# Scintillator_Circuit.net
KiCad netlist of a schematic drawn in Altium Designer
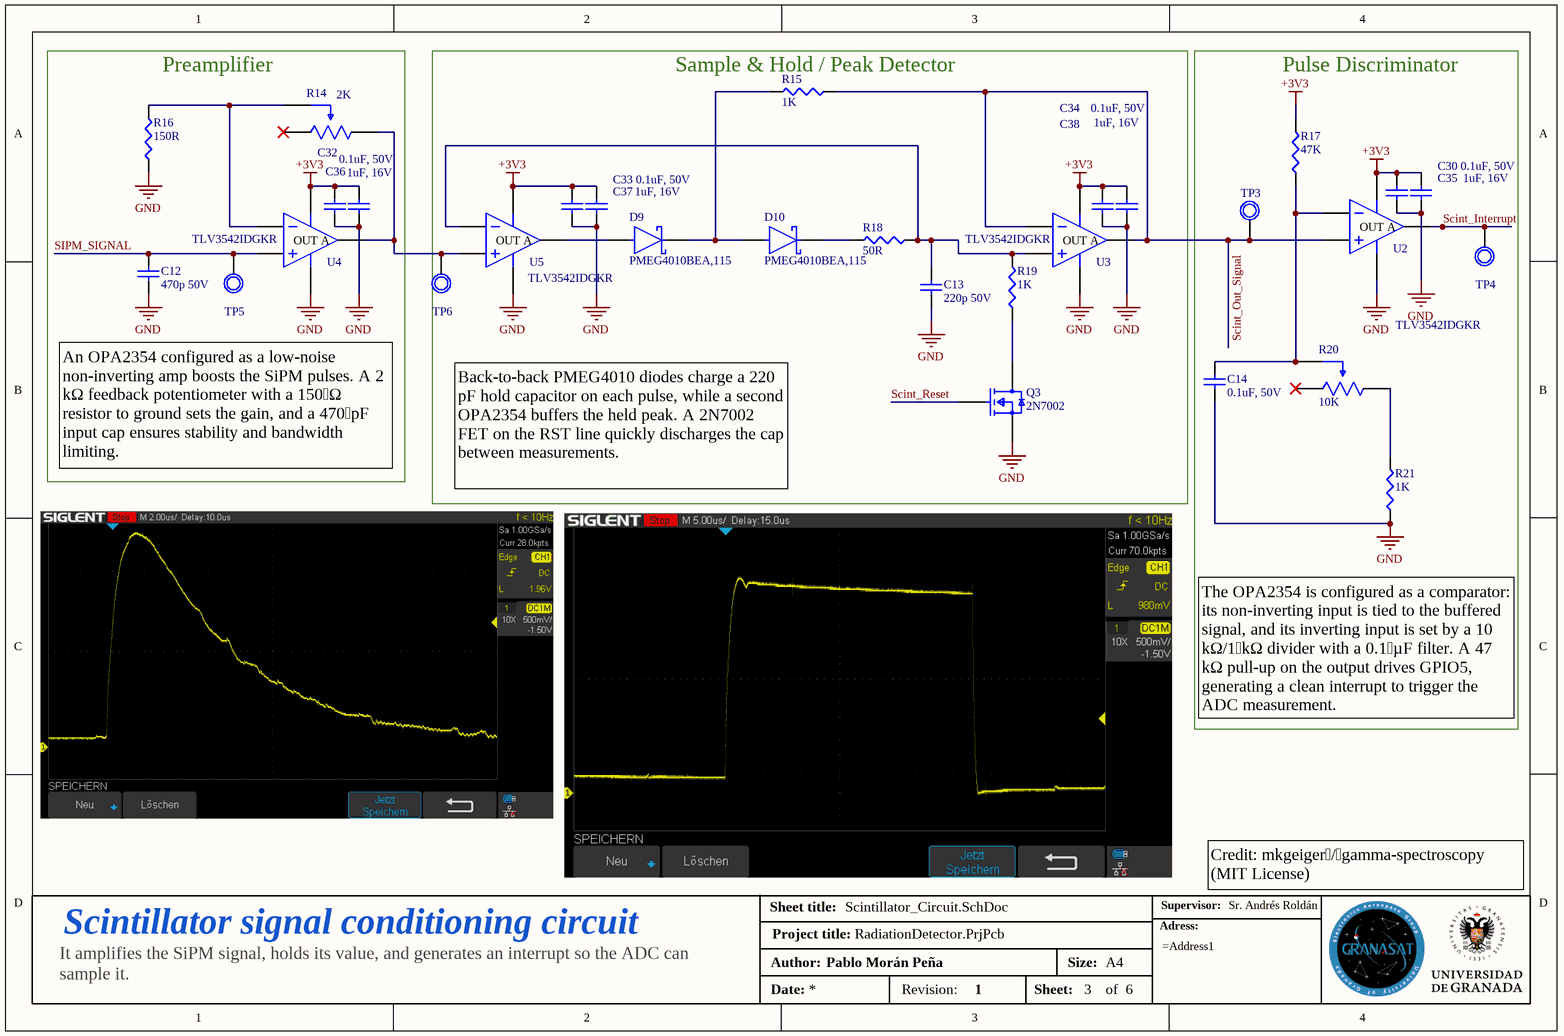
[diagram p0: Scintillator_Circuit.SchDoc]

(export (version "E")
  (design (tool "Eeschema 10.0.6"))
  (components
    (comp (ref "C12")
      (value "470p 50V")
      (footprint "CAP 0402_1005")
      (description "CAP CER 470PF 50V X7R 0402")
      (fields
        (field (name "MANUFACTURER") "Samsung")
        (field (name "MANUFACTURER PART NUMBER") "CL05B471KB5VPNC")
      )
      (libsource (lib "Schlib") (part "CL05B471KB5VPNC"))
    )
    (comp (ref "C13")
      (value "220p 50V")
      (footprint "CAP 0402_1005")
      (description "CAP CER 220PF 50V X7R 0402")
      (fields
        (field (name "MANUFACTURER") "Samsung")
        (field (name "MANUFACTURER PART NUMBER") "CL05B221KB5NNNC")
      )
      (libsource (lib "Schlib") (part "CL05B221KB5NNNC"))
    )
    (comp (ref "C14")
      (value "0.1uF, 50V")
      (footprint "CAP 0402_1005")
      (description "CAP CER 0.1UF 50V X7R 0402")
      (fields
        (field (name "MANUFACTURER") "Samsung")
        (field (name "MANUFACTURER PART NUMBER") "CL05B104KB5NNNC")
      )
      (libsource (lib "Schlib") (part "CL05B104KB5NNNC"))
    )
    (comp (ref "C30")
      (value "0.1uF, 50V")
      (footprint "CAP 0402_1005")
      (description "CAP CER 0.1UF 50V X7R 0402")
      (fields
        (field (name "MANUFACTURER") "Samsung")
        (field (name "MANUFACTURER PART NUMBER") "CL05B104KB5NNNC")
      )
      (libsource (lib "Schlib") (part "CL05B104KB5NNNC"))
    )
    (comp (ref "C32")
      (value "0.1uF, 50V")
      (footprint "CAP 0402_1005")
      (description "CAP CER 0.1UF 50V X7R 0402")
      (fields
        (field (name "MANUFACTURER") "Samsung")
        (field (name "MANUFACTURER PART NUMBER") "CL05B104KB5NNNC")
      )
      (libsource (lib "Schlib") (part "CL05B104KB5NNNC"))
    )
    (comp (ref "C33")
      (value "0.1uF, 50V")
      (footprint "CAP 0402_1005")
      (description "CAP CER 0.1UF 50V X7R 0402")
      (fields
        (field (name "MANUFACTURER") "Samsung")
        (field (name "MANUFACTURER PART NUMBER") "CL05B104KB5NNNC")
      )
      (libsource (lib "Schlib") (part "CL05B104KB5NNNC"))
    )
    (comp (ref "C34")
      (value "0.1uF, 50V")
      (footprint "CAP 0402_1005")
      (description "CAP CER 0.1UF 50V X7R 0402")
      (fields
        (field (name "MANUFACTURER") "Samsung")
        (field (name "MANUFACTURER PART NUMBER") "CL05B104KB5NNNC")
      )
      (libsource (lib "Schlib") (part "CL05B104KB5NNNC"))
    )
    (comp (ref "C35")
      (value "1uF, 16V")
      (footprint "CAP 0402_1005")
      (description "CAP CER 1UF 16V X5R 0402")
      (fields
        (field (name "MANUFACTURER") "Samsung Electro-Mechanics")
        (field (name "MANUFACTURER PART NUMBER") "CL05A105KO5NNNC")
      )
      (libsource (lib "Schlib") (part "CL05A105KO5NNNC"))
    )
    (comp (ref "C36")
      (value "1uF, 16V")
      (footprint "CAP 0402_1005")
      (description "CAP CER 1UF 16V X5R 0402")
      (fields
        (field (name "MANUFACTURER") "Samsung Electro-Mechanics")
        (field (name "MANUFACTURER PART NUMBER") "CL05A105KO5NNNC")
      )
      (libsource (lib "Schlib") (part "CL05A105KO5NNNC"))
    )
    (comp (ref "C37")
      (value "1uF, 16V")
      (footprint "CAP 0402_1005")
      (description "CAP CER 1UF 16V X5R 0402")
      (fields
        (field (name "MANUFACTURER") "Samsung Electro-Mechanics")
        (field (name "MANUFACTURER PART NUMBER") "CL05A105KO5NNNC")
      )
      (libsource (lib "Schlib") (part "CL05A105KO5NNNC"))
    )
    (comp (ref "C38")
      (value "1uF, 16V")
      (footprint "CAP 0402_1005")
      (description "CAP CER 1UF 16V X5R 0402")
      (fields
        (field (name "MANUFACTURER") "Samsung Electro-Mechanics")
        (field (name "MANUFACTURER PART NUMBER") "CL05A105KO5NNNC")
      )
      (libsource (lib "Schlib") (part "CL05A105KO5NNNC"))
    )
    (comp (ref "D9")
      (value "PMEG4010BEA,115")
      (footprint "SOD2512X110N")
      (description "DIODE SCHOTTKY 40V 1A SOD323")
      (fields (field (name "MANUFACTURER") "Nexperia") (field (name "LCSC PART NUMBER") "C36975"))
      (libsource (lib "Schlib") (part "PMEG4010BEA,115"))
    )
    (comp (ref "D10")
      (value "PMEG4010BEA,115")
      (footprint "SOD2512X110N")
      (description "DIODE SCHOTTKY 40V 1A SOD323")
      (fields (field (name "MANUFACTURER") "Nexperia") (field (name "LCSC PART NUMBER") "C36975"))
      (libsource (lib "Schlib") (part "PMEG4010BEA,115"))
    )
    (comp (ref "Q3")
      (value "2N7002")
      (footprint "SOT95P240X111-3N")
      (description "MOSFET SOT23 N 60V 5OHM 150C")
      (fields
        (field (name "MANUFACTURER") "ON Semiconductor / Fairchild")
        (field (name "LCSC PART NUMBER") "C124475")
      )
      (libsource (lib "Schlib") (part "2N7002"))
    )
    (comp (ref "R14")
      (value "2K")
      (footprint "TRIM_3314J-1-202E")
      (description "TRIMMER 2K OHM 0.25W J LEAD TOP")
      (fields (field (name "MANUFACTURER") "Bourns") (field (name "MANUFACTURER PART NUMBER") "3314J-1-202E"))
      (libsource (lib "Schlib") (part "3314J-1-202E"))
    )
    (comp (ref "R15")
      (value "1K")
      (footprint "RESC1005X37N")
      (description "RES SMD 1K OHM 5% 1/16W 0402")
      (fields
        (field (name "MANUFACTURER") "Yageo")
        (field (name "MANUFACTURER PART NUMBER") "AC0402JR-071KL")
      )
      (libsource (lib "Schlib") (part "AC0402JR-071KL"))
    )
    (comp (ref "R16")
      (value "150R")
      (footprint "RESC1005X37N")
      (description "RES SMD 150 OHM 1% 1/16W 0402")
      (fields
        (field (name "MANUFACTURER") "Yageo")
        (field (name "MANUFACTURER PART NUMBER") "AC0402FR-07150RL")
      )
      (libsource (lib "Schlib") (part "AC0402FR-07150RL"))
    )
    (comp (ref "R17")
      (value "47K")
      (footprint "RESC1005X37N")
      (description "RES SMD 47K OHM 1% 1/16W 0402")
      (fields
        (field (name "MANUFACTURER") "Yageo")
        (field (name "MANUFACTURER PART NUMBER") "AC0402FR-0747KL")
      )
      (libsource (lib "Schlib") (part "AC0402FR-0747KL"))
    )
    (comp (ref "R18")
      (value "50R")
      (footprint "RESC1005X37N")
      (description "RES SMD 50 OHM 0.1% 1/16W 0402")
      (fields
        (field (name "MANUFACTURER") "Yageo")
        (field (name "MANUFACTURER PART NUMBER") "RT0402BRE0750RL")
      )
      (libsource (lib "Schlib") (part "RT0402BRE0750RL"))
    )
    (comp (ref "R19")
      (value "1K")
      (footprint "RESC1005X37N")
      (description "RES SMD 1K OHM 5% 1/16W 0402")
      (fields
        (field (name "MANUFACTURER") "Yageo")
        (field (name "MANUFACTURER PART NUMBER") "AC0402JR-071KL")
      )
      (libsource (lib "Schlib") (part "AC0402JR-071KL"))
    )
    (comp (ref "R20")
      (value "10K")
      (footprint "TS53YL_VIS")
      (description "TRIMMER 10K OHM 0.25W GW TOP ADJ")
      (fields
        (field (name "MANUFACTURER") "Vishay")
        (field (name "MANUFACTURER PART NUMBER") "TS53YL103MR10")
      )
      (libsource (lib "Schlib") (part "TS53YL103MR10"))
    )
    (comp (ref "R21")
      (value "1K")
      (footprint "RESC1005X37N")
      (description "RES SMD 1K OHM 5% 1/16W 0402")
      (fields
        (field (name "MANUFACTURER") "Yageo")
        (field (name "MANUFACTURER PART NUMBER") "AC0402JR-071KL")
      )
      (libsource (lib "Schlib") (part "AC0402JR-071KL"))
    )
    (comp (ref "TP3")
      (value "Testpoint")
      (footprint "Testpoint")
      (libsource (lib "Schlib") (part "Testpoint"))
    )
    (comp (ref "TP4")
      (value "Testpoint")
      (footprint "Testpoint")
      (libsource (lib "Schlib") (part "Testpoint"))
    )
    (comp (ref "TP5")
      (value "Testpoint")
      (footprint "Testpoint")
      (libsource (lib "Schlib") (part "Testpoint"))
    )
    (comp (ref "TP6")
      (value "Testpoint")
      (footprint "Testpoint")
      (libsource (lib "Schlib") (part "Testpoint"))
    )
    (comp (ref "U2")
      (value "TLV3542IDGKR")
      (footprint "DGK0008A_M")
      (description "200MHz Rail-to-Rail I/O, CMOS Operational Amplifier for Cost-Sensitive Systems")
      (fields
        (field (name "MANUFACTURER") "Texas Instruments")
        (field (name "MANUFACTURER PART NUMBER") "OPA2354AIDGKR")
      )
      (libsource (lib "Schlib") (part "TLV3542IDGKR"))
    )
    (comp (ref "U3")
      (value "TLV3542IDGKR")
      (footprint "DGK0008A_M")
      (description "200MHz Rail-to-Rail I/O, CMOS Operational Amplifier for Cost-Sensitive Systems")
      (fields
        (field (name "MANUFACTURER") "Texas Instruments")
        (field (name "MANUFACTURER PART NUMBER") "OPA2354AIDGKR")
      )
      (libsource (lib "Schlib") (part "TLV3542IDGKR"))
    )
    (comp (ref "U4")
      (value "TLV3542IDGKR")
      (footprint "DGK0008A_M")
      (description "200MHz Rail-to-Rail I/O, CMOS Operational Amplifier for Cost-Sensitive Systems")
      (fields
        (field (name "MANUFACTURER") "Texas Instruments")
        (field (name "MANUFACTURER PART NUMBER") "OPA2354AIDGKR")
      )
      (libsource (lib "Schlib") (part "TLV3542IDGKR"))
    )
    (comp (ref "U5")
      (value "TLV3542IDGKR")
      (footprint "DGK0008A_M")
      (description "200MHz Rail-to-Rail I/O, CMOS Operational Amplifier for Cost-Sensitive Systems")
      (fields
        (field (name "MANUFACTURER") "Texas Instruments")
        (field (name "MANUFACTURER PART NUMBER") "OPA2354AIDGKR")
      )
      (libsource (lib "Schlib") (part "TLV3542IDGKR"))
    )
  )
  (nets
    (net (code "1") (name "+3V3") (class "Default")
      (node (ref "C30") (pin "2") (pinfunction "2_2") (pintype "passive"))
      (node (ref "C32") (pin "2") (pinfunction "2_2") (pintype "passive"))
      (node (ref "C33") (pin "2") (pinfunction "2_2") (pintype "passive"))
      (node (ref "C34") (pin "2") (pinfunction "2_2") (pintype "passive"))
      (node (ref "C35") (pin "2") (pinfunction "2_2") (pintype "passive"))
      (node (ref "C36") (pin "2") (pinfunction "2_2") (pintype "passive"))
      (node (ref "C37") (pin "2") (pinfunction "2_2") (pintype "passive"))
      (node (ref "C38") (pin "2") (pinfunction "2_2") (pintype "passive"))
      (node (ref "R17") (pin "2") (pinfunction "2_2") (pintype "passive"))
      (node (ref "U2") (pin "7") (pinfunction "V+_7") (pintype "power_in"))
      (node (ref "U3") (pin "7") (pinfunction "V+_7") (pintype "power_in"))
      (node (ref "U4") (pin "7") (pinfunction "V+_7") (pintype "power_in"))
      (node (ref "U5") (pin "7") (pinfunction "V+_7") (pintype "power_in"))
    )
    (net (code "2") (name "/SIPM_SIGNAL") (class "Default")
      (node (ref "C12") (pin "2") (pinfunction "2_2") (pintype "passive"))
      (node (ref "TP5") (pin "1") (pinfunction "1_1") (pintype "passive"))
      (node (ref "U4") (pin "3") (pinfunction "IN_A+_3") (pintype "passive"))
    )
    (net (code "3") (name "/Scint_Interrupt") (class "Default")
      (node (ref "TP4") (pin "1") (pinfunction "1_1") (pintype "passive"))
      (node (ref "U2") (pin "6") (pinfunction "OUT_A_6") (pintype "passive"))
    )
    (net (code "4") (name "/Scint_Out_Signal") (class "Default")
      (node (ref "R15") (pin "2") (pinfunction "2_2") (pintype "passive"))
      (node (ref "TP3") (pin "1") (pinfunction "1_1") (pintype "passive"))
      (node (ref "U2") (pin "3") (pinfunction "IN_A+_3") (pintype "passive"))
      (node (ref "U3") (pin "2") (pinfunction "IN_A-_2") (pintype "passive"))
      (node (ref "U3") (pin "6") (pinfunction "OUT_A_6") (pintype "passive"))
    )
    (net (code "5") (name "/Scint_Reset") (class "Default")
      (node (ref "Q3") (pin "1") (pinfunction "G_1") (pintype "passive"))
    )
    (net (code "6") (name "GND") (class "Default")
      (node (ref "C12") (pin "1") (pinfunction "1_1") (pintype "passive"))
      (node (ref "C13") (pin "1") (pinfunction "1_1") (pintype "passive"))
      (node (ref "C14") (pin "1") (pinfunction "1_1") (pintype "passive"))
      (node (ref "C30") (pin "1") (pinfunction "1_1") (pintype "passive"))
      (node (ref "C32") (pin "1") (pinfunction "1_1") (pintype "passive"))
      (node (ref "C33") (pin "1") (pinfunction "1_1") (pintype "passive"))
      (node (ref "C34") (pin "1") (pinfunction "1_1") (pintype "passive"))
      (node (ref "C35") (pin "1") (pinfunction "1_1") (pintype "passive"))
      (node (ref "C36") (pin "1") (pinfunction "1_1") (pintype "passive"))
      (node (ref "C37") (pin "1") (pinfunction "1_1") (pintype "passive"))
      (node (ref "C38") (pin "1") (pinfunction "1_1") (pintype "passive"))
      (node (ref "Q3") (pin "2") (pinfunction "S_2") (pintype "passive"))
      (node (ref "R16") (pin "1") (pinfunction "1_1") (pintype "passive"))
      (node (ref "R21") (pin "1") (pinfunction "1_1") (pintype "passive"))
      (node (ref "U2") (pin "4") (pinfunction "V-_4") (pintype "power_in"))
      (node (ref "U3") (pin "4") (pinfunction "V-_4") (pintype "power_in"))
      (node (ref "U4") (pin "4") (pinfunction "V-_4") (pintype "power_in"))
      (node (ref "U5") (pin "4") (pinfunction "V-_4") (pintype "power_in"))
    )
    (net (code "7") (name "Net-(D9-A)") (class "Default")
      (node (ref "D9") (pin "2") (pinfunction "A_2") (pintype "passive"))
      (node (ref "U5") (pin "6") (pinfunction "OUT_A_6") (pintype "passive"))
    )
    (net (code "8") (name "Net-(D10-A)") (class "Default")
      (node (ref "D10") (pin "2") (pinfunction "A_2") (pintype "passive"))
      (node (ref "D9") (pin "1") (pinfunction "C_1") (pintype "passive"))
      (node (ref "R15") (pin "1") (pinfunction "1_1") (pintype "passive"))
    )
    (net (code "9") (name "Net-(D10-C)") (class "Default")
      (node (ref "D10") (pin "1") (pinfunction "C_1") (pintype "passive"))
      (node (ref "R18") (pin "1") (pinfunction "1_1") (pintype "passive"))
    )
    (net (code "10") (name "Net-(Q3-D)") (class "Default")
      (node (ref "Q3") (pin "3") (pinfunction "D_3") (pintype "passive"))
      (node (ref "R19") (pin "1") (pinfunction "1_1") (pintype "passive"))
    )
    (net (code "11") (name "Net-(R14-CW)") (class "Default")
      (node (ref "R14") (pin "3") (pinfunction "CW_3") (pintype "passive"))
      (node (ref "TP6") (pin "1") (pinfunction "1_1") (pintype "passive"))
      (node (ref "U4") (pin "6") (pinfunction "OUT_A_6") (pintype "passive"))
      (node (ref "U5") (pin "3") (pinfunction "IN_A+_3") (pintype "passive"))
    )
    (net (code "12") (name "Net-(R14-WIPER)") (class "Default")
      (node (ref "R14") (pin "2") (pinfunction "WIPER_2") (pintype "passive"))
      (node (ref "R16") (pin "2") (pinfunction "2_2") (pintype "passive"))
      (node (ref "U4") (pin "2") (pinfunction "IN_A-_2") (pintype "passive"))
    )
    (net (code "13") (name "Net-(R20-CW)") (class "Default")
      (node (ref "R20") (pin "3") (pinfunction "CW_3") (pintype "passive"))
      (node (ref "R21") (pin "2") (pinfunction "2_2") (pintype "passive"))
    )
    (net (code "14") (name "Net-(R20-WIPER)") (class "Default")
      (node (ref "C14") (pin "2") (pinfunction "2_2") (pintype "passive"))
      (node (ref "R17") (pin "1") (pinfunction "1_1") (pintype "passive"))
      (node (ref "R20") (pin "2") (pinfunction "WIPER_2") (pintype "passive"))
      (node (ref "U2") (pin "2") (pinfunction "IN_A-_2") (pintype "passive"))
    )
    (net (code "15") (name "Net-(U3-IN_A+)") (class "Default")
      (node (ref "C13") (pin "2") (pinfunction "2_2") (pintype "passive"))
      (node (ref "R18") (pin "2") (pinfunction "2_2") (pintype "passive"))
      (node (ref "R19") (pin "2") (pinfunction "2_2") (pintype "passive"))
      (node (ref "U3") (pin "3") (pinfunction "IN_A+_3") (pintype "passive"))
      (node (ref "U5") (pin "2") (pinfunction "IN_A-_2") (pintype "passive"))
    )
    (net (code "16") (name "unconnected-(R14-CCW-Pad1)") (class "Default")
      (node (ref "R14") (pin "1") (pinfunction "CCW_1") (pintype "passive+no_connect"))
    )
    (net (code "17") (name "unconnected-(R20-CCW-Pad1)") (class "Default")
      (node (ref "R20") (pin "1") (pinfunction "CCW_1") (pintype "passive+no_connect"))
    )
  )
)
